# Interface.net
KiCad netlist of a schematic drawn in Altium Designer
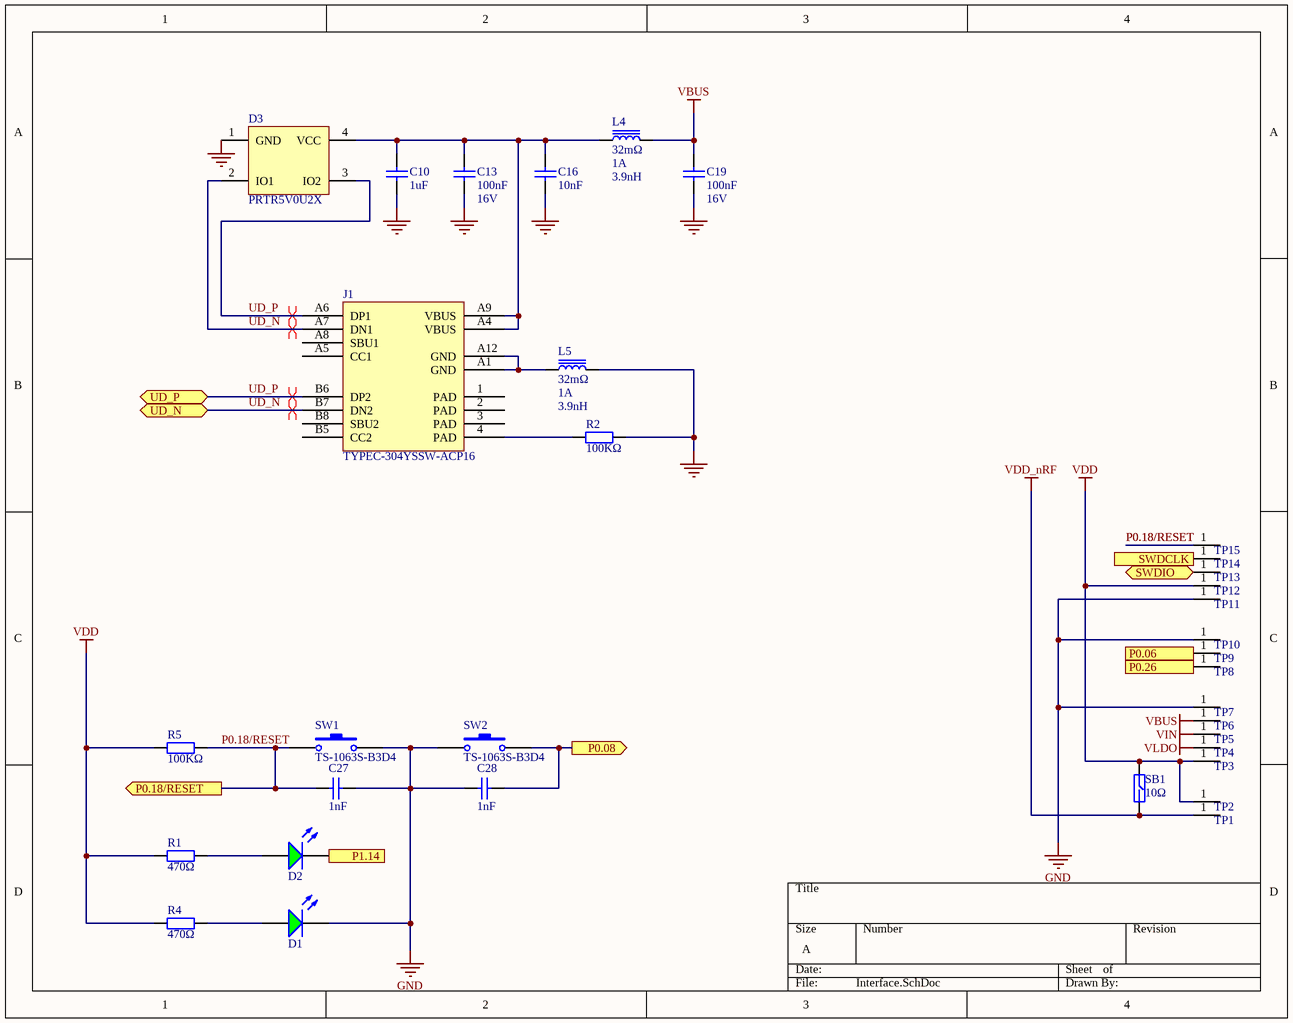
[diagram p0: Interface.SchDoc]

(export (version "E")
  (design (tool "Eeschema 10.0.6"))
  (components
    (comp (ref "C10")
      (value "1uF")
      (footprint "0603_C")
      (description "Chip Capacitor")
      (fields (field (name "VOLTAGE") "50V") (field (name "Comment") "1uF (105) 10% 50V"))
      (libsource (lib "LocalLib") (part "0603 1uF (105) 10% 50V"))
    )
    (comp (ref "C13")
      (value "100nF")
      (footprint "0402_C")
      (description "Chip Capacitor")
      (fields (field (name "VOLTAGE") "16V") (field (name "Comment") "100nF (104) 10% 16V"))
      (libsource (lib "LocalLib") (part "0402 100nF (104) 10% 16V"))
    )
    (comp (ref "C16")
      (value "10nF")
      (footprint "0402_C")
      (description "Chip Capacitor")
      (fields (field (name "VOLTAGE") "50V") (field (name "Comment") "10nF (103) 10% 50V"))
      (libsource (lib "LocalLib") (part "0402 10nF (103) 10% 50V"))
    )
    (comp (ref "C19")
      (value "100nF")
      (footprint "0402_C")
      (description "Chip Capacitor")
      (fields (field (name "VOLTAGE") "16V") (field (name "Comment") "100nF (104) 10% 16V"))
      (libsource (lib "LocalLib") (part "0402 100nF (104) 10% 16V"))
    )
    (comp (ref "C27")
      (value "1nF")
      (footprint "0402_C")
      (description "Chip Capacitor")
      (fields (field (name "VOLTAGE") "50V") (field (name "Comment") "1nF (102) 10% 50V"))
      (libsource (lib "LocalLib") (part "0402 1nF (102) 10% 50V"))
    )
    (comp (ref "C28")
      (value "1nF")
      (footprint "0402_C")
      (description "Chip Capacitor")
      (fields (field (name "VOLTAGE") "50V") (field (name "Comment") "1nF (102) 10% 50V"))
      (libsource (lib "LocalLib") (part "0402 1nF (102) 10% 50V"))
    )
    (comp (ref "D1")
      (value "0603 LED Green")
      (footprint "0603_LED_S1")
      (description "Green LED")
      (libsource (lib "LocalLib") (part "0603 LED Green"))
    )
    (comp (ref "D2")
      (value "0603 LED Green")
      (footprint "0603_LED_S1")
      (description "Green LED")
      (libsource (lib "LocalLib") (part "0603 LED Green"))
    )
    (comp (ref "D3")
      (value "PRTR5V0U2X")
      (footprint "SOT190P230X110-4L")
      (description "Ultra low capacitance double rail-to-rail ESD protection diode")
      (fields
        (field (name "MANUFACTURER") "NXP Semiconductors")
        (field (name "PUBLISHER") "Nordic Semiconductor")
        (field (name "AUTHOR") "rsk")
      )
      (libsource (lib "LocalLib") (part "PRTR5V0U2X"))
    )
    (comp (ref "J1")
      (value "TYPEC-304YSSW-ACP16")
      (footprint "TYPEC-304YSSW-ACP16")
      (description "5A16PIN TYPEC")
      (libsource (lib "LocalLib") (part "TYPEC-304YSSW-ACP16"))
    )
    (comp (ref "L4")
      (value "3.9nH")
      (footprint "0603_L")
      (description "1A 3.9nH 32mΩ 0603  Inductors (SMD) ROHS")
      (fields
        (field (name "DC RESISTANCE") "32mΩ")
        (field (name "CURRENT") "1A")
        (field (name "Comment") "LQW18AN3N9C10D")
      )
      (libsource (lib "LocalLib") (part "LQW18AN3N9C10D"))
    )
    (comp (ref "L5")
      (value "3.9nH")
      (footprint "0603_L")
      (description "1A 3.9nH 32mΩ 0603  Inductors (SMD) ROHS")
      (fields
        (field (name "DC RESISTANCE") "32mΩ")
        (field (name "CURRENT") "1A")
        (field (name "Comment") "LQW18AN3N9C10D")
      )
      (libsource (lib "LocalLib") (part "LQW18AN3N9C10D"))
    )
    (comp (ref "R1")
      (value "470Ω")
      (footprint "0402_R")
      (description "Chip Resistor")
      (fields (field (name "Comment") "470Ω (4700) ±1%"))
      (libsource (lib "LocalLib") (part "0402 470Ω (4700) 1%"))
    )
    (comp (ref "R2")
      (value "100KΩ")
      (footprint "0402_R")
      (description "Chip Resistor")
      (fields (field (name "Comment") "100KΩ (1003) ±1%"))
      (libsource (lib "LocalLib") (part "0402 100KΩ (1003) 1%"))
    )
    (comp (ref "R4")
      (value "470Ω")
      (footprint "0402_R")
      (description "Chip Resistor")
      (fields (field (name "Comment") "470Ω (4700) ±1%"))
      (libsource (lib "LocalLib") (part "0402 470Ω (4700) 1%"))
    )
    (comp (ref "R5")
      (value "100KΩ")
      (footprint "0402_R")
      (description "Chip Resistor")
      (fields (field (name "Comment") "100KΩ (1003) ±1%"))
      (libsource (lib "LocalLib") (part "0402 100KΩ (1003) 1%"))
    )
    (comp (ref "SB1")
      (value "10Ω")
      (footprint "0603-FUSE")
      (description "Fuse easy soldering for test, with 10Ω 0603 Resistor soldered")
      (libsource (lib "LocalLib") (part "Test-Fuse"))
    )
    (comp (ref "SW1")
      (value "TS-1063S-B3D4")
      (footprint "TS-1063S-B3D4")
      (description "SPST 250gf@±30gf -  Tactile Switches ROHS")
      (libsource (lib "LocalLib") (part "TS-1063S-B3D4"))
    )
    (comp (ref "SW2")
      (value "TS-1063S-B3D4")
      (footprint "TS-1063S-B3D4")
      (description "SPST 250gf@±30gf -  Tactile Switches ROHS")
      (libsource (lib "LocalLib") (part "TS-1063S-B3D4"))
    )
    (comp (ref "TP1")
      (value "Test Point")
      (footprint "TP_H_24_80_36")
      (libsource (lib "LocalLib") (part "Test-Point"))
    )
    (comp (ref "TP2")
      (value "Test Point")
      (footprint "TP_H_24_80_36")
      (libsource (lib "LocalLib") (part "Test-Point"))
    )
    (comp (ref "TP3")
      (value "Test Point")
      (footprint "TP_H_24_80_36")
      (libsource (lib "LocalLib") (part "Test-Point"))
    )
    (comp (ref "TP4")
      (value "Test Point")
      (footprint "TP_H_24_80_36")
      (libsource (lib "LocalLib") (part "Test-Point"))
    )
    (comp (ref "TP5")
      (value "Test Point")
      (footprint "TP_H_24_80_36")
      (libsource (lib "LocalLib") (part "Test-Point"))
    )
    (comp (ref "TP6")
      (value "Test Point")
      (footprint "TP_H_24_80_36")
      (libsource (lib "LocalLib") (part "Test-Point"))
    )
    (comp (ref "TP7")
      (value "Test Point")
      (footprint "TP_H_24_80_36")
      (libsource (lib "LocalLib") (part "Test-Point"))
    )
    (comp (ref "TP8")
      (value "Test Point")
      (footprint "TP_H_24_80_36")
      (libsource (lib "LocalLib") (part "Test-Point"))
    )
    (comp (ref "TP9")
      (value "Test Point")
      (footprint "TP_H_24_80_36")
      (libsource (lib "LocalLib") (part "Test-Point"))
    )
    (comp (ref "TP10")
      (value "Test Point")
      (footprint "TP_H_24_80_36")
      (libsource (lib "LocalLib") (part "Test-Point"))
    )
    (comp (ref "TP11")
      (value "Test Point")
      (footprint "TP_H_24_80_36")
      (libsource (lib "LocalLib") (part "Test-Point"))
    )
    (comp (ref "TP12")
      (value "Test Point")
      (footprint "TP_H_24_80_36")
      (libsource (lib "LocalLib") (part "Test-Point"))
    )
    (comp (ref "TP13")
      (value "Test Point")
      (footprint "TP_H_24_80_36")
      (libsource (lib "LocalLib") (part "Test-Point"))
    )
    (comp (ref "TP14")
      (value "Test Point")
      (footprint "TP_H_24_80_36")
      (libsource (lib "LocalLib") (part "Test-Point"))
    )
    (comp (ref "TP15")
      (value "Test Point")
      (footprint "TP_H_24_80_36")
      (libsource (lib "LocalLib") (part "Test-Point"))
    )
  )
  (nets
    (net (code "1") (name "/P0.06") (class "Default")
      (node (ref "TP9") (pin "1") (pinfunction "TP_1") (pintype "passive"))
    )
    (net (code "2") (name "/P0.08") (class "Default")
      (node (ref "C28") (pin "2") (pinfunction "2_2") (pintype "passive"))
      (node (ref "SW2") (pin "2") (pinfunction "2_2") (pintype "passive"))
    )
    (net (code "3") (name "/P0.18{slash}RESET") (class "Default")
      (node (ref "C27") (pin "1") (pinfunction "1_1") (pintype "passive"))
      (node (ref "R5") (pin "2") (pinfunction "2_2") (pintype "passive"))
      (node (ref "SW1") (pin "1") (pinfunction "1_1") (pintype "passive"))
      (node (ref "TP15") (pin "1") (pinfunction "TP_1") (pintype "passive"))
    )
    (net (code "4") (name "/P0.26") (class "Default")
      (node (ref "TP8") (pin "1") (pinfunction "TP_1") (pintype "passive"))
    )
    (net (code "5") (name "/P1.14") (class "Default")
      (node (ref "D2") (pin "K") (pinfunction "K_K") (pintype "passive"))
    )
    (net (code "6") (name "/SWDCLK") (class "Default")
      (node (ref "TP14") (pin "1") (pinfunction "TP_1") (pintype "passive"))
    )
    (net (code "7") (name "/SWDIO") (class "Default")
      (node (ref "TP13") (pin "1") (pinfunction "TP_1") (pintype "passive"))
    )
    (net (code "8") (name "/UD_N") (class "Default")
      (node (ref "D3") (pin "2") (pinfunction "IO1_2") (pintype "passive"))
      (node (ref "J1") (pin "A7") (pinfunction "DN1_A7") (pintype "passive"))
      (node (ref "J1") (pin "B7") (pinfunction "DN2_B7") (pintype "passive"))
    )
    (net (code "9") (name "/UD_P") (class "Default")
      (node (ref "D3") (pin "3") (pinfunction "IO2_3") (pintype "passive"))
      (node (ref "J1") (pin "A6") (pinfunction "DP1_A6") (pintype "passive"))
      (node (ref "J1") (pin "B6") (pinfunction "DP2_B6") (pintype "passive"))
    )
    (net (code "10") (name "GND") (class "Default")
      (node (ref "C10") (pin "1") (pinfunction "1_1") (pintype "passive"))
      (node (ref "C13") (pin "1") (pinfunction "1_1") (pintype "passive"))
      (node (ref "C16") (pin "1") (pinfunction "1_1") (pintype "passive"))
      (node (ref "C19") (pin "1") (pinfunction "1_1") (pintype "passive"))
      (node (ref "C27") (pin "2") (pinfunction "2_2") (pintype "passive"))
      (node (ref "C28") (pin "1") (pinfunction "1_1") (pintype "passive"))
      (node (ref "D1") (pin "K") (pinfunction "K_K") (pintype "passive"))
      (node (ref "D3") (pin "1") (pinfunction "GND_1") (pintype "passive"))
      (node (ref "L5") (pin "2") (pinfunction "2_2") (pintype "passive"))
      (node (ref "R2") (pin "2") (pinfunction "2_2") (pintype "passive"))
      (node (ref "SW1") (pin "2") (pinfunction "2_2") (pintype "passive"))
      (node (ref "SW2") (pin "1") (pinfunction "1_1") (pintype "passive"))
      (node (ref "TP10") (pin "1") (pinfunction "TP_1") (pintype "passive"))
      (node (ref "TP11") (pin "1") (pinfunction "TP_1") (pintype "passive"))
      (node (ref "TP7") (pin "1") (pinfunction "TP_1") (pintype "passive"))
    )
    (net (code "11") (name "Net-(D1-PadA)") (class "Default")
      (node (ref "D1") (pin "A") (pinfunction "A_A") (pintype "passive"))
      (node (ref "R4") (pin "2") (pinfunction "2_2") (pintype "passive"))
    )
    (net (code "12") (name "Net-(D2-PadA)") (class "Default")
      (node (ref "D2") (pin "A") (pinfunction "A_A") (pintype "passive"))
      (node (ref "R1") (pin "2") (pinfunction "2_2") (pintype "passive"))
    )
    (net (code "13") (name "Net-(D3-VCC)") (class "Default")
      (node (ref "C10") (pin "2") (pinfunction "2_2") (pintype "passive"))
      (node (ref "C13") (pin "2") (pinfunction "2_2") (pintype "passive"))
      (node (ref "C16") (pin "2") (pinfunction "2_2") (pintype "passive"))
      (node (ref "D3") (pin "4") (pinfunction "VCC_4") (pintype "passive"))
      (node (ref "J1") (pin "A4") (pinfunction "VBUS_A4") (pintype "passive"))
      (node (ref "J1") (pin "A9") (pinfunction "VBUS_A9") (pintype "passive"))
      (node (ref "L4") (pin "1") (pinfunction "1_1") (pintype "passive"))
    )
    (net (code "14") (name "Net-(J1-GND-PadA1)") (class "Default")
      (node (ref "J1") (pin "A1") (pinfunction "GND_A1") (pintype "passive"))
      (node (ref "J1") (pin "A12") (pinfunction "GND_A12") (pintype "passive"))
      (node (ref "L5") (pin "1") (pinfunction "1_1") (pintype "passive"))
    )
    (net (code "15") (name "Net-(J1-PAD-Pad4)") (class "Default")
      (node (ref "J1") (pin "4") (pinfunction "PAD_4") (pintype "passive"))
      (node (ref "R2") (pin "1") (pinfunction "1_1") (pintype "passive"))
    )
    (net (code "16") (name "VBUS") (class "Default")
      (node (ref "C19") (pin "2") (pinfunction "2_2") (pintype "passive"))
      (node (ref "L4") (pin "2") (pinfunction "2_2") (pintype "passive"))
      (node (ref "TP6") (pin "1") (pinfunction "TP_1") (pintype "passive"))
    )
    (net (code "17") (name "VDD") (class "Default")
      (node (ref "R1") (pin "1") (pinfunction "1_1") (pintype "passive"))
      (node (ref "R4") (pin "1") (pinfunction "1_1") (pintype "passive"))
      (node (ref "R5") (pin "1") (pinfunction "1_1") (pintype "passive"))
      (node (ref "SB1") (pin "1") (pinfunction "1_1") (pintype "passive"))
      (node (ref "TP12") (pin "1") (pinfunction "TP_1") (pintype "passive"))
      (node (ref "TP2") (pin "1") (pinfunction "TP_1") (pintype "passive"))
      (node (ref "TP3") (pin "1") (pinfunction "TP_1") (pintype "passive"))
    )
    (net (code "18") (name "VDD_nRF") (class "Default")
      (node (ref "SB1") (pin "2") (pinfunction "2_2") (pintype "passive"))
      (node (ref "TP1") (pin "1") (pinfunction "TP_1") (pintype "passive"))
    )
    (net (code "19") (name "VIN") (class "Default")
      (node (ref "TP5") (pin "1") (pinfunction "TP_1") (pintype "passive"))
    )
    (net (code "20") (name "VLDO") (class "Default")
      (node (ref "TP4") (pin "1") (pinfunction "TP_1") (pintype "passive"))
    )
    (net (code "21") (name "unconnected-(J1-CC1-PadA5)") (class "Default")
      (node (ref "J1") (pin "A5") (pinfunction "CC1_A5") (pintype "passive"))
    )
    (net (code "22") (name "unconnected-(J1-CC2-PadB5)") (class "Default")
      (node (ref "J1") (pin "B5") (pinfunction "CC2_B5") (pintype "passive"))
    )
    (net (code "23") (name "unconnected-(J1-PAD-Pad1)") (class "Default")
      (node (ref "J1") (pin "1") (pinfunction "PAD_1") (pintype "passive"))
    )
    (net (code "24") (name "unconnected-(J1-PAD-Pad2)") (class "Default")
      (node (ref "J1") (pin "2") (pinfunction "PAD_2") (pintype "passive"))
    )
    (net (code "25") (name "unconnected-(J1-PAD-Pad3)") (class "Default")
      (node (ref "J1") (pin "3") (pinfunction "PAD_3") (pintype "passive"))
    )
    (net (code "26") (name "unconnected-(J1-SBU1-PadA8)") (class "Default")
      (node (ref "J1") (pin "A8") (pinfunction "SBU1_A8") (pintype "passive"))
    )
    (net (code "27") (name "unconnected-(J1-SBU2-PadB8)") (class "Default")
      (node (ref "J1") (pin "B8") (pinfunction "SBU2_B8") (pintype "passive"))
    )
  )
)
